# Wifi.net
KiCad netlist of a schematic drawn in Altium Designer
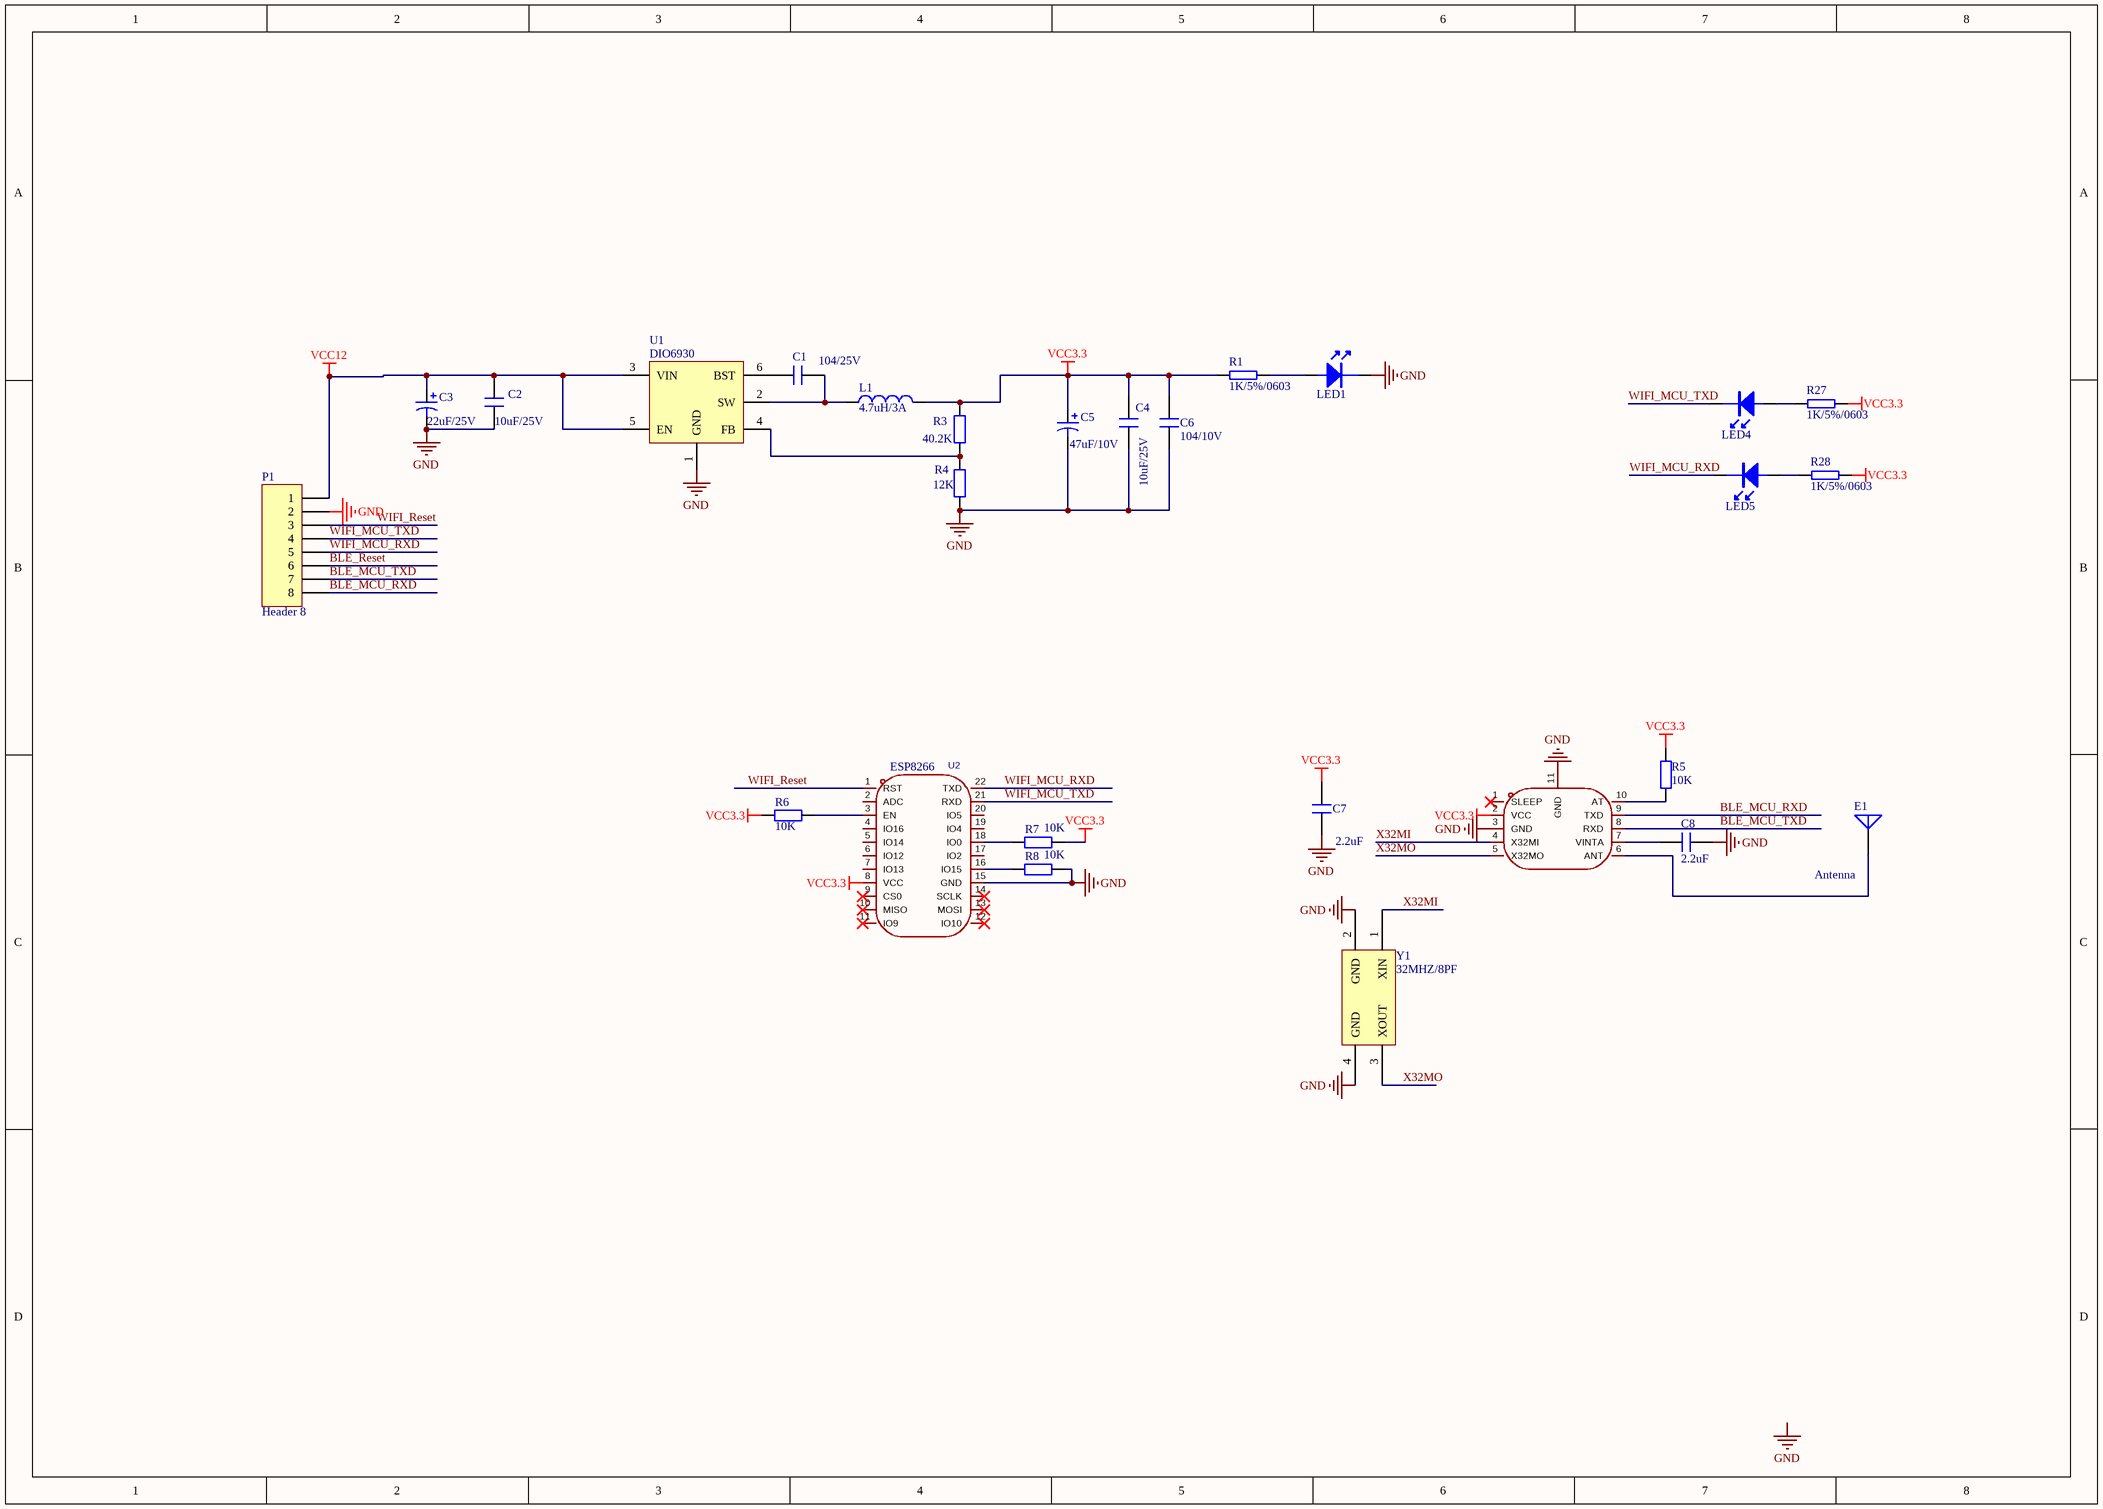
[diagram p0: Wifi.SchDoc]

(export (version "E")
  (design (tool "Eeschema 10.0.6"))
  (components
    (comp (ref "C1") (value "104/25V") (footprint "0603R") (libsource (lib "ES_Schematic") (part "CAP_1")))
    (comp (ref "C2") (value "10uF/25V") (footprint "0603R") (libsource (lib "ES_Schematic") (part "CAP")))
    (comp (ref "C3")
      (value "22uF/25V")
      (footprint "0805R")
      (description "Polarized Capacitor (Radial)")
      (fields (field (name "PUBLISHER") "Altium Limited"))
      (libsource (lib "Miscellaneous Devices") (part "Cap Pol1"))
    )
    (comp (ref "C4") (value "10uF/25V") (footprint "0603R") (libsource (lib "ES_Schematic") (part "CAP")))
    (comp (ref "C5")
      (value "47uF/10V")
      (footprint "0805R")
      (description "Polarized Capacitor (Radial)")
      (fields (field (name "PUBLISHER") "Altium Limited"))
      (libsource (lib "Miscellaneous Devices") (part "Cap Pol1"))
    )
    (comp (ref "C6") (value "104/10V") (footprint "0603R") (libsource (lib "ES_Schematic") (part "CAP_1")))
    (comp (ref "C7") (value "2.2uF") (footprint "0603R") (libsource (lib "ES_Schematic") (part "CAP_1")))
    (comp (ref "C8") (value "2.2uF") (footprint "0603R") (libsource (lib "ES_Schematic") (part "CAP_1")))
    (comp (ref "E1")
      (value "Antenna")
      (footprint "ANT-F-1-2.4G-1.6mmFR4-WCH")
      (description "Generic Antenna")
      (fields (field (name "PUBLISHER") "Altium Limited"))
      (libsource (lib "Miscellaneous Devices") (part "Antenna"))
    )
    (comp (ref "L1")
      (value "4.7uH/3A")
      (footprint "CD54")
      (description "Inductor")
      (fields (field (name "PUBLISHER") "Altium Limited"))
      (libsource (lib "Miscellaneous Devices") (part "Inductor"))
    )
    (comp (ref "LED1") (value "LED") (footprint "0603LED") (libsource (lib "ES_Schematic") (part "LED")))
    (comp (ref "LED4") (value "LED") (footprint "0603LED") (libsource (lib "ES_Schematic") (part "LED")))
    (comp (ref "LED5") (value "LED") (footprint "0603LED") (libsource (lib "ES_Schematic") (part "LED")))
    (comp (ref "P1")
      (value "Header 8")
      (footprint "HDR1X8")
      (description "Header, 8-Pin")
      (fields (field (name "PUBLISHER") "Altium Limited"))
      (libsource (lib "Miscellaneous Connectors") (part "Header 8"))
    )
    (comp (ref "R1") (value "1K/5%/0603") (footprint "0603R") (libsource (lib "ES_Schematic") (part "RES")))
    (comp (ref "R3")
      (value "40.2K")
      (footprint "0603R")
      (description "Resistor")
      (fields (field (name "PUBLISHER") "Altium Limited"))
      (libsource (lib "") (part "Res2_2"))
    )
    (comp (ref "R4")
      (value "12K")
      (footprint "0603R")
      (description "Resistor")
      (fields (field (name "PUBLISHER") "Altium Limited"))
      (libsource (lib "") (part "Res2_2"))
    )
    (comp (ref "R5")
      (value "10K")
      (footprint "0603R")
      (description "Resistor")
      (fields (field (name "PUBLISHER") "Altium Limited"))
      (libsource (lib "") (part "Res2_1"))
    )
    (comp (ref "R6")
      (value "10K")
      (footprint "0603R")
      (description "Resistor")
      (fields (field (name "PUBLISHER") "Altium Limited"))
      (libsource (lib "Miscellaneous Devices") (part "Res2"))
    )
    (comp (ref "R7")
      (value "10K")
      (footprint "0603R")
      (description "Resistor")
      (fields (field (name "PUBLISHER") "Altium Limited"))
      (libsource (lib "Miscellaneous Devices") (part "Res2"))
    )
    (comp (ref "R8")
      (value "10K")
      (footprint "0603R")
      (description "Resistor")
      (fields (field (name "PUBLISHER") "Altium Limited"))
      (libsource (lib "Miscellaneous Devices") (part "Res2"))
    )
    (comp (ref "R27") (value "1K/5%/0603") (footprint "0603R") (libsource (lib "ES_Schematic") (part "RES")))
    (comp (ref "R28") (value "1K/5%/0603") (footprint "0603R") (libsource (lib "ES_Schematic") (part "RES")))
    (comp (ref "U1")
      (value "DIO6930")
      (footprint "SOT-23-6DBV")
      (libsource (lib "ES_Schematic") (part "BL8032"))
    )
    (comp (ref "U2")
      (value "ESP8266")
      (footprint "ESP12E")
      (libsource (lib "altium-import") (part "root_0_ESP-12E_"))
    )
    (comp (ref "U3")
      (value "CH9141K")
      (footprint "CH9141K")
      (libsource (lib "altium-import") (part "root_0_CH9141K_"))
    )
    (comp (ref "Y1") (value "32MHZ/8PF") (footprint "3225") (libsource (lib "others") (part "12MHz无源")))
  )
  (nets
    (net (code "1") (name "/BLE_MCU_RXD") (class "Default")
      (node (ref "P1") (pin "8") (pinfunction "8_8") (pintype "passive"))
      (node (ref "U3") (pin "9") (pinfunction "TXD_9") (pintype "passive"))
    )
    (net (code "2") (name "/BLE_MCU_TXD") (class "Default")
      (node (ref "P1") (pin "7") (pinfunction "7_7") (pintype "passive"))
      (node (ref "U3") (pin "8") (pinfunction "RXD_8") (pintype "passive"))
    )
    (net (code "3") (name "/BLE_Reset") (class "Default")
      (node (ref "P1") (pin "6") (pinfunction "6_6") (pintype "passive"))
    )
    (net (code "4") (name "/WIFI_MCU_RXD") (class "Default")
      (node (ref "LED5") (pin "2") (pinfunction "2_2") (pintype "passive"))
      (node (ref "P1") (pin "5") (pinfunction "5_5") (pintype "passive"))
      (node (ref "U2") (pin "22") (pinfunction "TXD_22") (pintype "passive"))
    )
    (net (code "5") (name "/WIFI_MCU_TXD") (class "Default")
      (node (ref "LED4") (pin "2") (pinfunction "2_2") (pintype "passive"))
      (node (ref "P1") (pin "4") (pinfunction "4_4") (pintype "passive"))
      (node (ref "U2") (pin "21") (pinfunction "RXD_21") (pintype "passive"))
    )
    (net (code "6") (name "/WIFI_Reset") (class "Default")
      (node (ref "P1") (pin "3") (pinfunction "3_3") (pintype "passive"))
      (node (ref "U2") (pin "1") (pinfunction "RST_1") (pintype "passive"))
    )
    (net (code "7") (name "/X32MI") (class "Default")
      (node (ref "U3") (pin "4") (pinfunction "X32MI_4") (pintype "passive"))
      (node (ref "Y1") (pin "1") (pinfunction "XIN_1") (pintype "passive"))
    )
    (net (code "8") (name "/X32MO") (class "Default")
      (node (ref "U3") (pin "5") (pinfunction "X32MO_5") (pintype "passive"))
      (node (ref "Y1") (pin "3") (pinfunction "XOUT_3") (pintype "passive"))
    )
    (net (code "9") (name "GND") (class "Default")
      (node (ref "C2") (pin "1") (pinfunction "1_1") (pintype "passive"))
      (node (ref "C3") (pin "2") (pinfunction "2_2") (pintype "passive"))
      (node (ref "C4") (pin "1") (pinfunction "1_1") (pintype "passive"))
      (node (ref "C5") (pin "2") (pinfunction "2_2") (pintype "passive"))
      (node (ref "C6") (pin "1") (pinfunction "1_1") (pintype "passive"))
      (node (ref "C7") (pin "1") (pinfunction "1_1") (pintype "passive"))
      (node (ref "C8") (pin "1") (pinfunction "1_1") (pintype "passive"))
      (node (ref "LED1") (pin "2") (pinfunction "2_2") (pintype "passive"))
      (node (ref "P1") (pin "2") (pinfunction "2_2") (pintype "passive"))
      (node (ref "R4") (pin "2") (pinfunction "2_2") (pintype "passive"))
      (node (ref "R8") (pin "2") (pinfunction "2_2") (pintype "passive"))
      (node (ref "U1") (pin "1") (pinfunction "GND_1") (pintype "passive"))
      (node (ref "U2") (pin "15") (pinfunction "GND_15") (pintype "passive"))
      (node (ref "U3") (pin "11") (pinfunction "GND_11") (pintype "passive"))
      (node (ref "U3") (pin "3") (pinfunction "GND_3") (pintype "passive"))
      (node (ref "Y1") (pin "2") (pinfunction "GND_2") (pintype "passive"))
      (node (ref "Y1") (pin "4") (pinfunction "GND_4") (pintype "passive"))
    )
    (net (code "10") (name "Net-(E1-A)") (class "Default")
      (node (ref "E1") (pin "1") (pinfunction "A_1") (pintype "passive"))
      (node (ref "U3") (pin "6") (pinfunction "ANT_6") (pintype "passive"))
    )
    (net (code "11") (name "Net-(LED1-Pad1)") (class "Default")
      (node (ref "LED1") (pin "1") (pinfunction "1_1") (pintype "passive"))
      (node (ref "R1") (pin "2") (pinfunction "2_2") (pintype "passive"))
    )
    (net (code "12") (name "Net-(LED4-Pad1)") (class "Default")
      (node (ref "LED4") (pin "1") (pinfunction "1_1") (pintype "passive"))
      (node (ref "R27") (pin "2") (pinfunction "2_2") (pintype "passive"))
    )
    (net (code "13") (name "Net-(LED5-Pad1)") (class "Default")
      (node (ref "LED5") (pin "1") (pinfunction "1_1") (pintype "passive"))
      (node (ref "R28") (pin "2") (pinfunction "2_2") (pintype "passive"))
    )
    (net (code "14") (name "Net-(U1-BST)") (class "Default")
      (node (ref "C1") (pin "2") (pinfunction "2_2") (pintype "passive"))
      (node (ref "U1") (pin "6") (pinfunction "BST_6") (pintype "passive"))
    )
    (net (code "15") (name "Net-(U1-FB)") (class "Default")
      (node (ref "R3") (pin "2") (pinfunction "2_2") (pintype "passive"))
      (node (ref "R4") (pin "1") (pinfunction "1_1") (pintype "passive"))
      (node (ref "U1") (pin "4") (pinfunction "FB_4") (pintype "passive"))
    )
    (net (code "16") (name "Net-(U1-SW)") (class "Default")
      (node (ref "C1") (pin "1") (pinfunction "1_1") (pintype "passive"))
      (node (ref "L1") (pin "1") (pinfunction "1_1") (pintype "passive"))
      (node (ref "U1") (pin "2") (pinfunction "SW_2") (pintype "passive"))
    )
    (net (code "17") (name "Net-(U2-EN)") (class "Default")
      (node (ref "R6") (pin "2") (pinfunction "2_2") (pintype "passive"))
      (node (ref "U2") (pin "3") (pinfunction "EN_3") (pintype "passive"))
    )
    (net (code "18") (name "Net-(U2-IO0)") (class "Default")
      (node (ref "R7") (pin "1") (pinfunction "1_1") (pintype "passive"))
      (node (ref "U2") (pin "18") (pinfunction "IO0_18") (pintype "passive"))
    )
    (net (code "19") (name "Net-(U2-IO15)") (class "Default")
      (node (ref "R8") (pin "1") (pinfunction "1_1") (pintype "passive"))
      (node (ref "U2") (pin "16") (pinfunction "IO15_16") (pintype "passive"))
    )
    (net (code "20") (name "Net-(U3-AT)") (class "Default")
      (node (ref "R5") (pin "1") (pinfunction "1_1") (pintype "passive"))
      (node (ref "U3") (pin "10") (pinfunction "AT_10") (pintype "passive"))
    )
    (net (code "21") (name "Net-(U3-VINTA)") (class "Default")
      (node (ref "C8") (pin "2") (pinfunction "2_2") (pintype "passive"))
      (node (ref "U3") (pin "7") (pinfunction "VINTA_7") (pintype "passive"))
    )
    (net (code "22") (name "VCC3.3") (class "Default")
      (node (ref "C4") (pin "2") (pinfunction "2_2") (pintype "passive"))
      (node (ref "C5") (pin "1") (pinfunction "1_1") (pintype "passive"))
      (node (ref "C6") (pin "2") (pinfunction "2_2") (pintype "passive"))
      (node (ref "C7") (pin "2") (pinfunction "2_2") (pintype "passive"))
      (node (ref "L1") (pin "2") (pinfunction "2_2") (pintype "passive"))
      (node (ref "R1") (pin "1") (pinfunction "1_1") (pintype "passive"))
      (node (ref "R27") (pin "1") (pinfunction "1_1") (pintype "passive"))
      (node (ref "R28") (pin "1") (pinfunction "1_1") (pintype "passive"))
      (node (ref "R3") (pin "1") (pinfunction "1_1") (pintype "passive"))
      (node (ref "R5") (pin "2") (pinfunction "2_2") (pintype "passive"))
      (node (ref "R6") (pin "1") (pinfunction "1_1") (pintype "passive"))
      (node (ref "R7") (pin "2") (pinfunction "2_2") (pintype "passive"))
      (node (ref "U2") (pin "8") (pinfunction "VCC_8") (pintype "passive"))
      (node (ref "U3") (pin "2") (pinfunction "VCC_2") (pintype "passive"))
    )
    (net (code "23") (name "VCC12") (class "Default")
      (node (ref "C2") (pin "2") (pinfunction "2_2") (pintype "passive"))
      (node (ref "C3") (pin "1") (pinfunction "1_1") (pintype "passive"))
      (node (ref "P1") (pin "1") (pinfunction "1_1") (pintype "passive"))
      (node (ref "U1") (pin "3") (pinfunction "VIN_3") (pintype "passive"))
      (node (ref "U1") (pin "5") (pinfunction "EN_5") (pintype "passive"))
    )
    (net (code "24") (name "unconnected-(U2-ADC-Pad2)") (class "Default")
      (node (ref "U2") (pin "2") (pinfunction "ADC_2") (pintype "passive"))
    )
    (net (code "25") (name "unconnected-(U2-CS0-Pad9)") (class "Default")
      (node (ref "U2") (pin "9") (pinfunction "CS0_9") (pintype "passive+no_connect"))
    )
    (net (code "26") (name "unconnected-(U2-IO2-Pad17)") (class "Default")
      (node (ref "U2") (pin "17") (pinfunction "IO2_17") (pintype "passive"))
    )
    (net (code "27") (name "unconnected-(U2-IO4-Pad19)") (class "Default")
      (node (ref "U2") (pin "19") (pinfunction "IO4_19") (pintype "passive"))
    )
    (net (code "28") (name "unconnected-(U2-IO5-Pad20)") (class "Default")
      (node (ref "U2") (pin "20") (pinfunction "IO5_20") (pintype "passive"))
    )
    (net (code "29") (name "unconnected-(U2-IO9-Pad11)") (class "Default")
      (node (ref "U2") (pin "11") (pinfunction "IO9_11") (pintype "passive+no_connect"))
    )
    (net (code "30") (name "unconnected-(U2-IO10-Pad12)") (class "Default")
      (node (ref "U2") (pin "12") (pinfunction "IO10_12") (pintype "passive+no_connect"))
    )
    (net (code "31") (name "unconnected-(U2-IO12-Pad6)") (class "Default")
      (node (ref "U2") (pin "6") (pinfunction "IO12_6") (pintype "passive"))
    )
    (net (code "32") (name "unconnected-(U2-IO13-Pad7)") (class "Default")
      (node (ref "U2") (pin "7") (pinfunction "IO13_7") (pintype "passive"))
    )
    (net (code "33") (name "unconnected-(U2-IO14-Pad5)") (class "Default")
      (node (ref "U2") (pin "5") (pinfunction "IO14_5") (pintype "passive"))
    )
    (net (code "34") (name "unconnected-(U2-IO16-Pad4)") (class "Default")
      (node (ref "U2") (pin "4") (pinfunction "IO16_4") (pintype "passive"))
    )
    (net (code "35") (name "unconnected-(U2-MISO-Pad10)") (class "Default")
      (node (ref "U2") (pin "10") (pinfunction "MISO_10") (pintype "passive+no_connect"))
    )
    (net (code "36") (name "unconnected-(U2-MOSI-Pad13)") (class "Default")
      (node (ref "U2") (pin "13") (pinfunction "MOSI_13") (pintype "passive+no_connect"))
    )
    (net (code "37") (name "unconnected-(U2-SCLK-Pad14)") (class "Default")
      (node (ref "U2") (pin "14") (pinfunction "SCLK_14") (pintype "passive+no_connect"))
    )
    (net (code "38") (name "unconnected-(U3-SLEEP-Pad1)") (class "Default")
      (node (ref "U3") (pin "1") (pinfunction "SLEEP_1") (pintype "passive+no_connect"))
    )
  )
)
